# LED_IF_circuit2.net
KiCad netlist of a schematic drawn in EAGLE
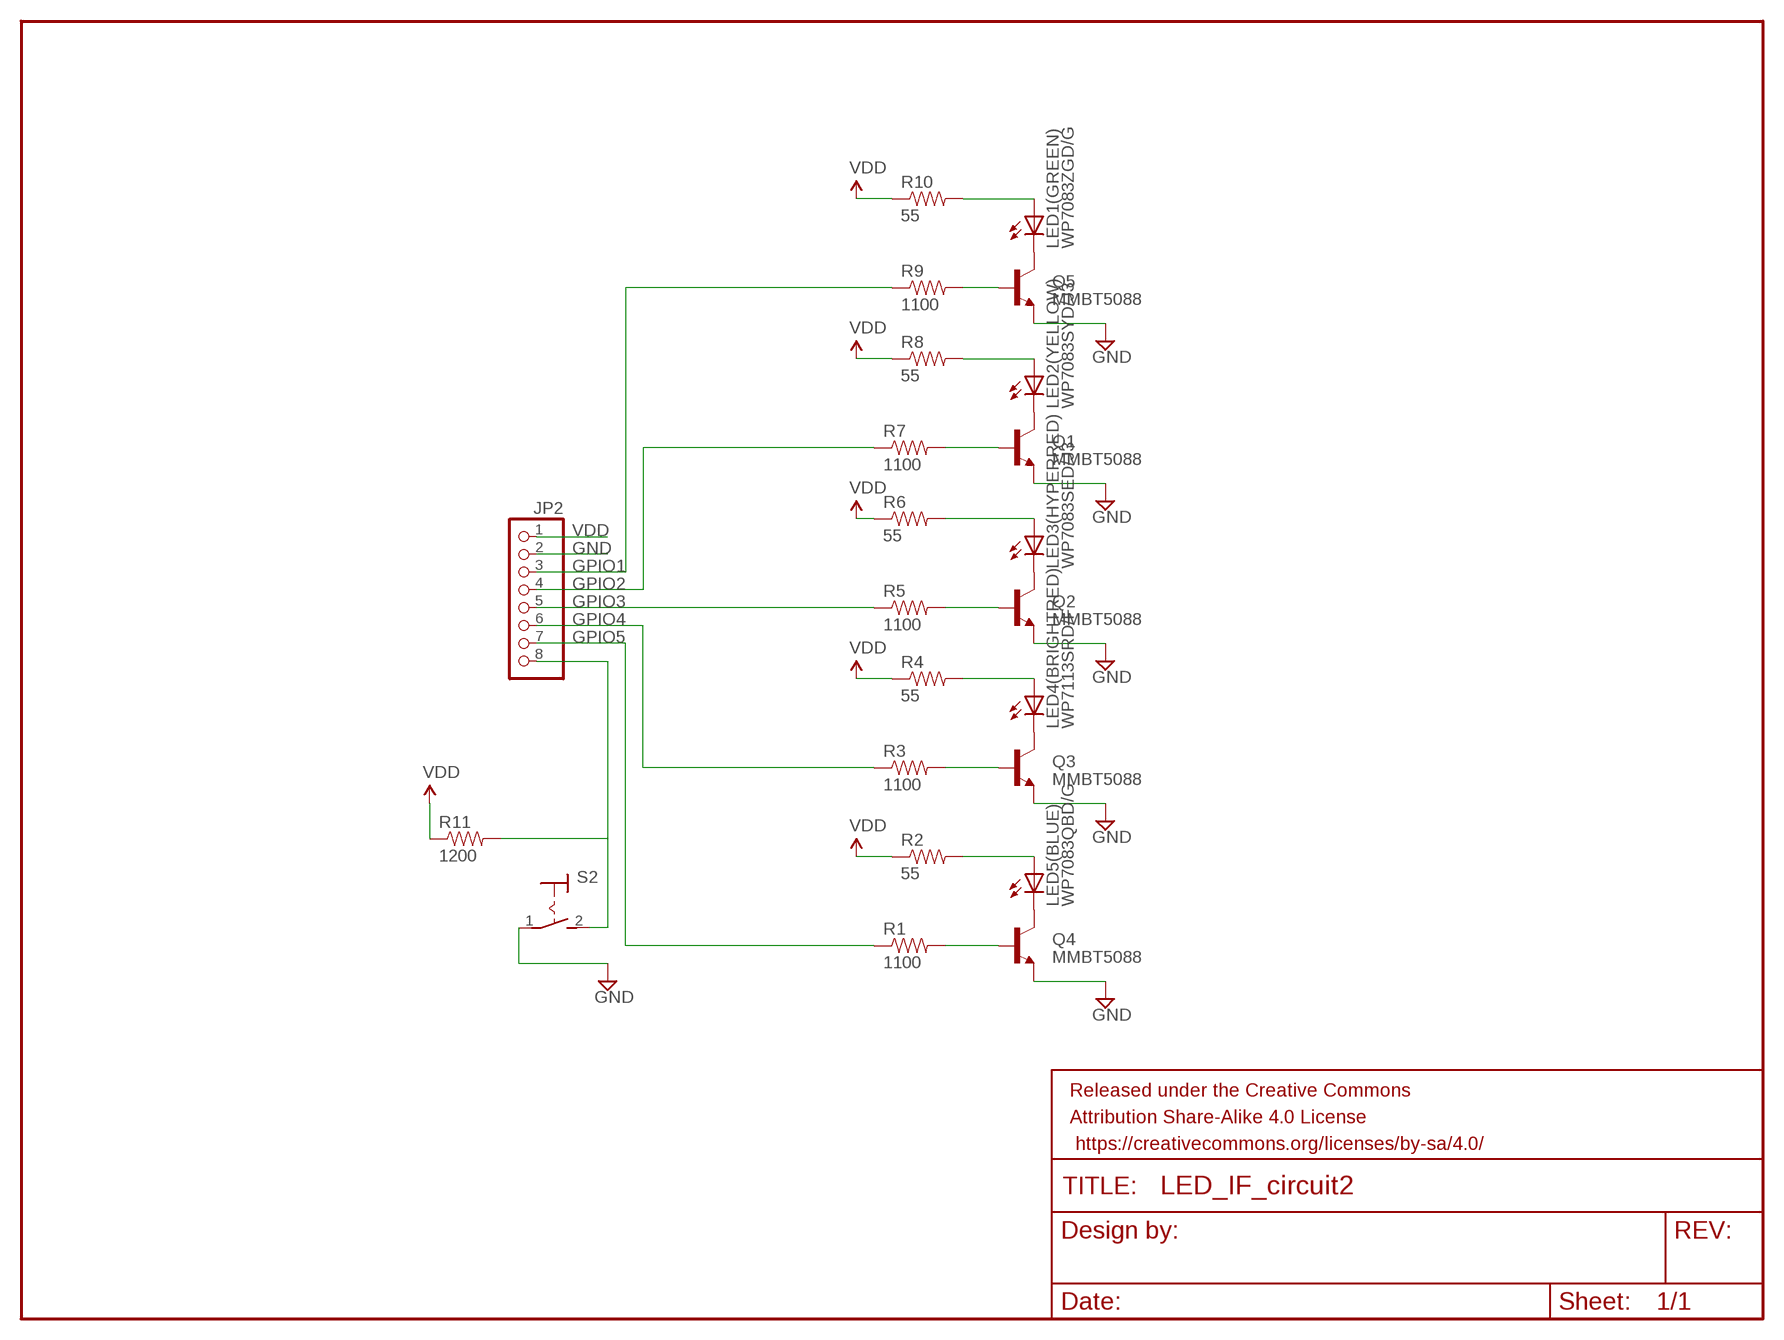
[diagram p0: schematic, sheet 1]

(export (version "E")
  (design (tool "Eeschema 10.0.6"))
  (components
    (comp (ref "FRAME1")
      (value "FRAME-LETTERNO_PACKAGE")
      (footprint "eagle-import:DUMMY")
      (fields (field (name "DESIGNER") "Nobody"))
      (libsource (lib "eagle-import") (part "FRAME-LETTERNO_PACKAGE"))
    )
    (comp (ref "JP2")
      (value "PINHD-1X8")
      (footprint "eagle-import:1X08")
      (libsource (lib "eagle-import") (part "PINHD-1X8"))
    )
    (comp (ref "LED1(GREEN)")
      (value "WP7083ZGD/G")
      (footprint "eagle-import:LED5MM")
      (libsource (lib "eagle-import") (part "LED5MM"))
    )
    (comp (ref "LED2(YELLOW)")
      (value "WP7083SYD/J3")
      (footprint "eagle-import:LED5MM")
      (libsource (lib "eagle-import") (part "LED5MM"))
    )
    (comp (ref "LED3(HYPERRED)")
      (value "WP7083SED/J3")
      (footprint "eagle-import:LED5MM")
      (libsource (lib "eagle-import") (part "LED5MM"))
    )
    (comp (ref "LED4(BRIGHTRED)")
      (value "WP7113SRD/F")
      (footprint "eagle-import:LED5MM")
      (libsource (lib "eagle-import") (part "LED5MM"))
    )
    (comp (ref "LED5(BLUE)")
      (value "WP7083QBD/G")
      (footprint "eagle-import:LED5MM")
      (libsource (lib "eagle-import") (part "LED5MM"))
    )
    (comp (ref "Q1")
      (value "MMBT5088")
      (footprint "eagle-import:SOT23-3")
      (libsource (lib "eagle-import") (part "TRANSISTOR_NPNMMBT5088"))
    )
    (comp (ref "Q2")
      (value "MMBT5088")
      (footprint "eagle-import:SOT23-3")
      (libsource (lib "eagle-import") (part "TRANSISTOR_NPNMMBT5088"))
    )
    (comp (ref "Q3")
      (value "MMBT5088")
      (footprint "eagle-import:SOT23-3")
      (libsource (lib "eagle-import") (part "TRANSISTOR_NPNMMBT5088"))
    )
    (comp (ref "Q4")
      (value "MMBT5088")
      (footprint "eagle-import:SOT23-3")
      (libsource (lib "eagle-import") (part "TRANSISTOR_NPNMMBT5088"))
    )
    (comp (ref "Q5")
      (value "MMBT5088")
      (footprint "eagle-import:SOT23-3")
      (libsource (lib "eagle-import") (part "TRANSISTOR_NPNMMBT5088"))
    )
    (comp (ref "R1")
      (value "1100")
      (footprint "eagle-import:0603-RES")
      (libsource (lib "eagle-import") (part "RESISTOR0603-RES"))
    )
    (comp (ref "R2")
      (value "55")
      (footprint "eagle-import:0603-RES")
      (libsource (lib "eagle-import") (part "RESISTOR0603-RES"))
    )
    (comp (ref "R3")
      (value "1100")
      (footprint "eagle-import:0603-RES")
      (libsource (lib "eagle-import") (part "RESISTOR0603-RES"))
    )
    (comp (ref "R4")
      (value "55")
      (footprint "eagle-import:0603-RES")
      (libsource (lib "eagle-import") (part "RESISTOR0603-RES"))
    )
    (comp (ref "R5")
      (value "1100")
      (footprint "eagle-import:0603-RES")
      (libsource (lib "eagle-import") (part "RESISTOR0603-RES"))
    )
    (comp (ref "R6")
      (value "55")
      (footprint "eagle-import:0603-RES")
      (libsource (lib "eagle-import") (part "RESISTOR0603-RES"))
    )
    (comp (ref "R7")
      (value "1100")
      (footprint "eagle-import:0603-RES")
      (libsource (lib "eagle-import") (part "RESISTOR0603-RES"))
    )
    (comp (ref "R8")
      (value "55")
      (footprint "eagle-import:0603-RES")
      (libsource (lib "eagle-import") (part "RESISTOR0603-RES"))
    )
    (comp (ref "R9")
      (value "1100")
      (footprint "eagle-import:0603-RES")
      (libsource (lib "eagle-import") (part "RESISTOR0603-RES"))
    )
    (comp (ref "R10")
      (value "55")
      (footprint "eagle-import:0603-RES")
      (libsource (lib "eagle-import") (part "RESISTOR0603-RES"))
    )
    (comp (ref "R11")
      (value "1200")
      (footprint "eagle-import:0603-RES")
      (libsource (lib "eagle-import") (part "RESISTOR0603-RES"))
    )
    (comp (ref "S2")
      (value "MS243TMS6T5B2M2RETMS6T5B2M2RE")
      (footprint "eagle-import:MS243")
      (libsource (lib "eagle-import") (part "MS243TMS6T5B2M2RETMS6T5B2M2RE"))
    )
  )
  (nets
    (net (code "1") (name "/GPIO1") (class "Default")
      (node (ref "JP2") (pin "3") (pinfunction "3_3") (pintype "passive"))
      (node (ref "R9") (pin "1") (pinfunction "1_1") (pintype "passive"))
    )
    (net (code "2") (name "/GPIO2") (class "Default")
      (node (ref "JP2") (pin "4") (pinfunction "4_4") (pintype "passive"))
      (node (ref "R7") (pin "1") (pinfunction "1_1") (pintype "passive"))
    )
    (net (code "3") (name "/GPIO3") (class "Default")
      (node (ref "JP2") (pin "5") (pinfunction "5_5") (pintype "passive"))
      (node (ref "R5") (pin "1") (pinfunction "1_1") (pintype "passive"))
    )
    (net (code "4") (name "/GPIO4") (class "Default")
      (node (ref "JP2") (pin "6") (pinfunction "6_6") (pintype "passive"))
      (node (ref "R3") (pin "1") (pinfunction "1_1") (pintype "passive"))
    )
    (net (code "5") (name "/GPIO5") (class "Default")
      (node (ref "JP2") (pin "7") (pinfunction "7_7") (pintype "passive"))
      (node (ref "R1") (pin "1") (pinfunction "1_1") (pintype "passive"))
    )
    (net (code "6") (name "GND") (class "Default")
      (node (ref "JP2") (pin "2") (pinfunction "2_2") (pintype "passive"))
      (node (ref "Q1") (pin "2") (pinfunction "E_2") (pintype "passive"))
      (node (ref "Q2") (pin "2") (pinfunction "E_2") (pintype "passive"))
      (node (ref "Q3") (pin "2") (pinfunction "E_2") (pintype "passive"))
      (node (ref "Q4") (pin "2") (pinfunction "E_2") (pintype "passive"))
      (node (ref "Q5") (pin "2") (pinfunction "E_2") (pintype "passive"))
      (node (ref "S2") (pin "1") (pinfunction "P_1") (pintype "passive"))
    )
    (net (code "7") (name "Net-(LED1(GREEN)-C)") (class "Default")
      (node (ref "LED1(GREEN)") (pin "K") (pinfunction "C_K") (pintype "passive"))
      (node (ref "Q5") (pin "3") (pinfunction "C_3") (pintype "passive"))
    )
    (net (code "8") (name "Net-(LED1(GREEN)-PadA)") (class "Default")
      (node (ref "LED1(GREEN)") (pin "A") (pinfunction "A_A") (pintype "passive"))
      (node (ref "R10") (pin "2") (pinfunction "2_2") (pintype "passive"))
    )
    (net (code "9") (name "Net-(LED2(YELLOW)-C)") (class "Default")
      (node (ref "LED2(YELLOW)") (pin "K") (pinfunction "C_K") (pintype "passive"))
      (node (ref "Q1") (pin "3") (pinfunction "C_3") (pintype "passive"))
    )
    (net (code "10") (name "Net-(LED2(YELLOW)-PadA)") (class "Default")
      (node (ref "LED2(YELLOW)") (pin "A") (pinfunction "A_A") (pintype "passive"))
      (node (ref "R8") (pin "2") (pinfunction "2_2") (pintype "passive"))
    )
    (net (code "11") (name "Net-(LED3(HYPERRED)-C)") (class "Default")
      (node (ref "LED3(HYPERRED)") (pin "K") (pinfunction "C_K") (pintype "passive"))
      (node (ref "Q2") (pin "3") (pinfunction "C_3") (pintype "passive"))
    )
    (net (code "12") (name "Net-(LED3(HYPERRED)-PadA)") (class "Default")
      (node (ref "LED3(HYPERRED)") (pin "A") (pinfunction "A_A") (pintype "passive"))
      (node (ref "R6") (pin "2") (pinfunction "2_2") (pintype "passive"))
    )
    (net (code "13") (name "Net-(LED4(BRIGHTRED)-C)") (class "Default")
      (node (ref "LED4(BRIGHTRED)") (pin "K") (pinfunction "C_K") (pintype "passive"))
      (node (ref "Q3") (pin "3") (pinfunction "C_3") (pintype "passive"))
    )
    (net (code "14") (name "Net-(LED4(BRIGHTRED)-PadA)") (class "Default")
      (node (ref "LED4(BRIGHTRED)") (pin "A") (pinfunction "A_A") (pintype "passive"))
      (node (ref "R4") (pin "2") (pinfunction "2_2") (pintype "passive"))
    )
    (net (code "15") (name "Net-(LED5(BLUE)-C)") (class "Default")
      (node (ref "LED5(BLUE)") (pin "K") (pinfunction "C_K") (pintype "passive"))
      (node (ref "Q4") (pin "3") (pinfunction "C_3") (pintype "passive"))
    )
    (net (code "16") (name "Net-(LED5(BLUE)-PadA)") (class "Default")
      (node (ref "LED5(BLUE)") (pin "A") (pinfunction "A_A") (pintype "passive"))
      (node (ref "R2") (pin "2") (pinfunction "2_2") (pintype "passive"))
    )
    (net (code "17") (name "Net-(Q1-B)") (class "Default")
      (node (ref "Q1") (pin "1") (pinfunction "B_1") (pintype "passive"))
      (node (ref "R7") (pin "2") (pinfunction "2_2") (pintype "passive"))
    )
    (net (code "18") (name "Net-(Q2-B)") (class "Default")
      (node (ref "Q2") (pin "1") (pinfunction "B_1") (pintype "passive"))
      (node (ref "R5") (pin "2") (pinfunction "2_2") (pintype "passive"))
    )
    (net (code "19") (name "Net-(Q3-B)") (class "Default")
      (node (ref "Q3") (pin "1") (pinfunction "B_1") (pintype "passive"))
      (node (ref "R3") (pin "2") (pinfunction "2_2") (pintype "passive"))
    )
    (net (code "20") (name "Net-(Q4-B)") (class "Default")
      (node (ref "Q4") (pin "1") (pinfunction "B_1") (pintype "passive"))
      (node (ref "R1") (pin "2") (pinfunction "2_2") (pintype "passive"))
    )
    (net (code "21") (name "Net-(Q5-B)") (class "Default")
      (node (ref "Q5") (pin "1") (pinfunction "B_1") (pintype "passive"))
      (node (ref "R9") (pin "2") (pinfunction "2_2") (pintype "passive"))
    )
    (net (code "22") (name "Net-(S2-S)") (class "Default")
      (node (ref "JP2") (pin "8") (pinfunction "8_8") (pintype "passive"))
      (node (ref "R11") (pin "2") (pinfunction "2_2") (pintype "passive"))
      (node (ref "S2") (pin "2") (pinfunction "S_2") (pintype "passive"))
    )
    (net (code "23") (name "VDD") (class "Default")
      (node (ref "JP2") (pin "1") (pinfunction "1_1") (pintype "passive"))
      (node (ref "R10") (pin "1") (pinfunction "1_1") (pintype "passive"))
      (node (ref "R11") (pin "1") (pinfunction "1_1") (pintype "passive"))
      (node (ref "R2") (pin "1") (pinfunction "1_1") (pintype "passive"))
      (node (ref "R4") (pin "1") (pinfunction "1_1") (pintype "passive"))
      (node (ref "R6") (pin "1") (pinfunction "1_1") (pintype "passive"))
      (node (ref "R8") (pin "1") (pinfunction "1_1") (pintype "passive"))
    )
  )
)
